# AMU-S28-V00-USBCProtection.net
KiCad netlist of a schematic drawn in Altium Designer
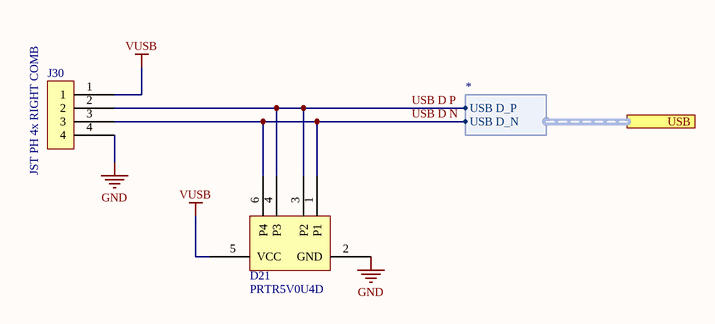
[diagram p0: AMU-S28-V00-USBCProtection.SchDoc]

(export (version "E")
  (design (tool "Eeschema 10.0.6"))
  (components
    (comp (ref "D21")
      (value "PRTR5V0U4D")
      (footprint "SC-47")
      (description "Clamp Ipp Tvs Diode Surface Mount 6-TSOP")
      (libsource (lib "QUTMS-MCISOLibrary") (part "PRTR5V0U4D"))
    )
    (comp (ref "J30")
      (value "JST PH 4x RIGHT COMB")
      (footprint "JST PH 4x RIGHT COMB")
      (libsource (lib "QUTMS-MCISOLibrary") (part "JST PH 4x RIGHT COMB"))
    )
  )
  (nets
    (net (code "2") (name "/USB D N") (class "Default")
      (node (ref "D21") (pin "1") (pinfunction "P1_1") (pintype "passive"))
      (node (ref "D21") (pin "6") (pinfunction "P4_6") (pintype "passive"))
      (node (ref "J30") (pin "3") (pinfunction "3_3") (pintype "passive"))
    )
    (net (code "3") (name "/USB D P") (class "Default")
      (node (ref "D21") (pin "3") (pinfunction "P2_3") (pintype "passive"))
      (node (ref "D21") (pin "4") (pinfunction "P3_4") (pintype "passive"))
      (node (ref "J30") (pin "2") (pinfunction "2_2") (pintype "passive"))
    )
    (net (code "5") (name "GND") (class "Default")
      (node (ref "D21") (pin "2") (pinfunction "GND_2") (pintype "passive"))
      (node (ref "J30") (pin "4") (pinfunction "4_4") (pintype "passive"))
    )
    (net (code "6") (name "VUSB") (class "Default")
      (node (ref "D21") (pin "5") (pinfunction "VCC_5") (pintype "passive"))
      (node (ref "J30") (pin "1") (pinfunction "1_1") (pintype "passive"))
    )
  )
)
